# v2_7_Schematic.net
KiCad netlist of a schematic drawn in EAGLE
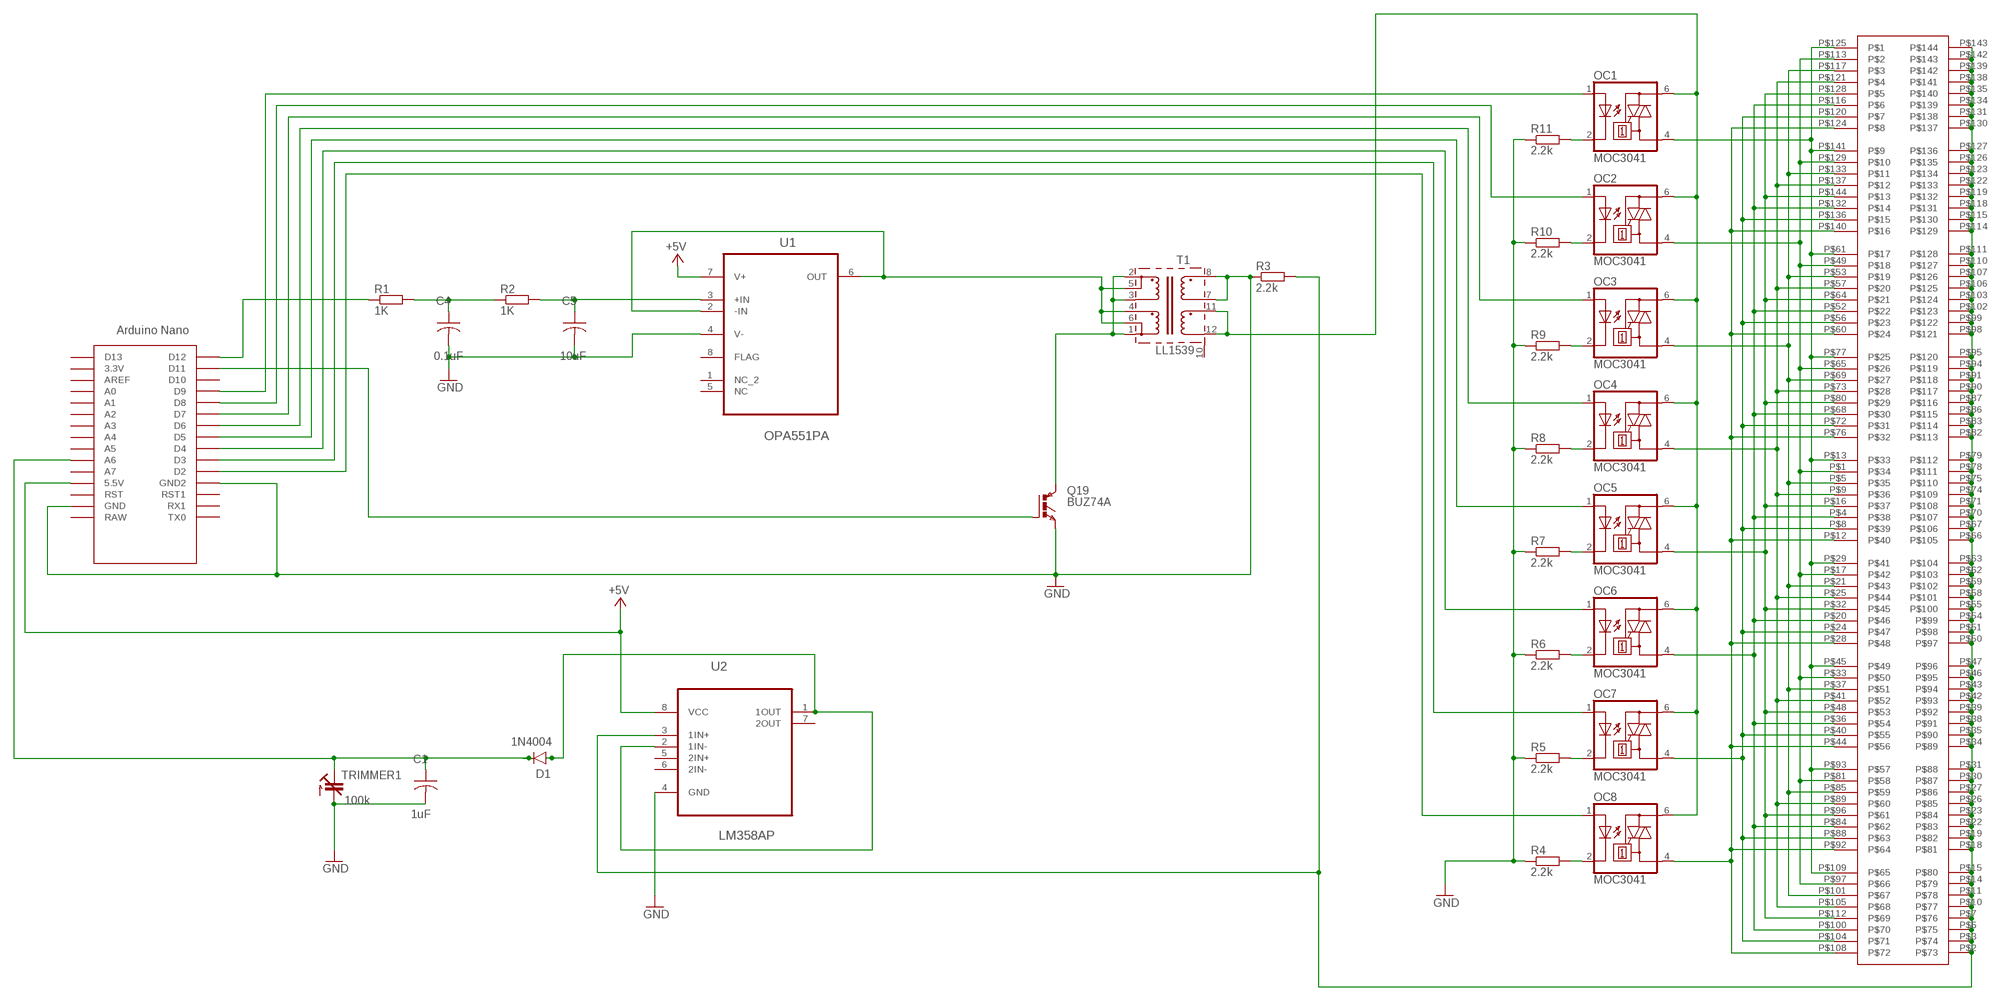
[diagram p0: schematic, sheet 1]

(export (version "E")
  (design (tool "Eeschema 10.0.6"))
  (components
    (comp (ref "C1")
      (value "1uF")
      (footprint "eagle-import:CAP_RADIAL_2MM")
      (fields
        (field (name "DIGIKEY_PART_NUMBER") "P5178-ND")
        (field (name "MANUFACTURER") "Panasonic Electronic Components")
        (field (name "MPN") "ECA-1HM100")
        (field (name "CREATED_BY") "PCBLayout.com")
      )
      (libsource (lib "eagle-import") (part "ECA-1HM100"))
    )
    (comp (ref "C4")
      (value "0.1uF")
      (footprint "eagle-import:CAP_RADIAL_2MM")
      (fields
        (field (name "DIGIKEY_PART_NUMBER") "P5178-ND")
        (field (name "MANUFACTURER") "Panasonic Electronic Components")
        (field (name "MPN") "ECA-1HM100")
        (field (name "CREATED_BY") "PCBLayout.com")
      )
      (libsource (lib "eagle-import") (part "ECA-1HM100"))
    )
    (comp (ref "C5")
      (value "10uF")
      (footprint "eagle-import:CAP_RADIAL_2MM")
      (fields
        (field (name "DIGIKEY_PART_NUMBER") "P5178-ND")
        (field (name "MANUFACTURER") "Panasonic Electronic Components")
        (field (name "MPN") "ECA-1HM100")
        (field (name "CREATED_BY") "PCBLayout.com")
      )
      (libsource (lib "eagle-import") (part "ECA-1HM100"))
    )
    (comp (ref "D1")
      (value "1N4004")
      (footprint "eagle-import:DO-41")
      (fields
        (field (name "DIGIKEY_PART_NUMBER") "1N4004MSCT-ND")
        (field (name "MANUFACTURER") "Micro Commercial Co")
        (field (name "CREATED_BY") "PCBLayout.com")
      )
      (libsource (lib "eagle-import") (part "1N4004"))
    )
    (comp (ref "OC1")
      (value "MOC3041")
      (footprint "eagle-import:DIL06")
      (libsource (lib "eagle-import") (part "MOC3041"))
    )
    (comp (ref "OC2")
      (value "MOC3041")
      (footprint "eagle-import:DIL06")
      (libsource (lib "eagle-import") (part "MOC3041"))
    )
    (comp (ref "OC3")
      (value "MOC3041")
      (footprint "eagle-import:DIL06")
      (libsource (lib "eagle-import") (part "MOC3041"))
    )
    (comp (ref "OC4")
      (value "MOC3041")
      (footprint "eagle-import:DIL06")
      (libsource (lib "eagle-import") (part "MOC3041"))
    )
    (comp (ref "OC5")
      (value "MOC3041")
      (footprint "eagle-import:DIL06")
      (libsource (lib "eagle-import") (part "MOC3041"))
    )
    (comp (ref "OC6")
      (value "MOC3041")
      (footprint "eagle-import:DIL06")
      (libsource (lib "eagle-import") (part "MOC3041"))
    )
    (comp (ref "OC7")
      (value "MOC3041")
      (footprint "eagle-import:DIL06")
      (libsource (lib "eagle-import") (part "MOC3041"))
    )
    (comp (ref "OC8")
      (value "MOC3041")
      (footprint "eagle-import:DIL06")
      (libsource (lib "eagle-import") (part "MOC3041"))
    )
    (comp (ref "Q19")
      (value "BUZ74A")
      (footprint "eagle-import:TO220AV")
      (libsource (lib "eagle-import") (part "IGBTTO220AV"))
    )
    (comp (ref "R1")
      (value "1K")
      (footprint "eagle-import:0204V")
      (libsource (lib "eagle-import") (part "R-EU_0204/2V"))
    )
    (comp (ref "R2")
      (value "1K")
      (footprint "eagle-import:0204V")
      (libsource (lib "eagle-import") (part "R-EU_0204/2V"))
    )
    (comp (ref "R3")
      (value "2.2k")
      (footprint "eagle-import:0204V")
      (libsource (lib "eagle-import") (part "R-EU_0204/2V"))
    )
    (comp (ref "R4")
      (value "2.2k")
      (footprint "eagle-import:0204V")
      (libsource (lib "eagle-import") (part "R-EU_0204/2V"))
    )
    (comp (ref "R5")
      (value "2.2k")
      (footprint "eagle-import:0204V")
      (libsource (lib "eagle-import") (part "R-EU_0204/2V"))
    )
    (comp (ref "R6")
      (value "2.2k")
      (footprint "eagle-import:0204V")
      (libsource (lib "eagle-import") (part "R-EU_0204/2V"))
    )
    (comp (ref "R7")
      (value "2.2k")
      (footprint "eagle-import:0204V")
      (libsource (lib "eagle-import") (part "R-EU_0204/2V"))
    )
    (comp (ref "R8")
      (value "2.2k")
      (footprint "eagle-import:0204V")
      (libsource (lib "eagle-import") (part "R-EU_0204/2V"))
    )
    (comp (ref "R9")
      (value "2.2k")
      (footprint "eagle-import:0204V")
      (libsource (lib "eagle-import") (part "R-EU_0204/2V"))
    )
    (comp (ref "R10")
      (value "2.2k")
      (footprint "eagle-import:0204V")
      (libsource (lib "eagle-import") (part "R-EU_0204/2V"))
    )
    (comp (ref "R11")
      (value "2.2k")
      (footprint "eagle-import:0204V")
      (libsource (lib "eagle-import") (part "R-EU_0204/2V"))
    )
    (comp (ref "T1")
      (value "LL1539")
      (footprint "eagle-import:LL1539")
      (libsource (lib "eagle-import") (part "LL1539"))
    )
    (comp (ref "TRIMMER1")
      (value "100k")
      (footprint "eagle-import:CTRIM3040.452")
      (libsource (lib "eagle-import") (part "C-TRIMM3040.452"))
    )
    (comp (ref "U$1")
      (value "NANO")
      (footprint "eagle-import:NANO")
      (libsource (lib "eagle-import") (part "NANO"))
    )
    (comp (ref "U$2")
      (value "DOTS_V2")
      (footprint "eagle-import:DOTS_V2")
      (libsource (lib "eagle-import") (part "DOTS_V2"))
    )
    (comp (ref "U1")
      (value "OPA551PA")
      (footprint "eagle-import:DIP254P762X508-8")
      (libsource (lib "eagle-import") (part "OPA551PA"))
    )
    (comp (ref "U2")
      (value "LM358AP")
      (footprint "eagle-import:DIP254P762X508-8")
      (libsource (lib "eagle-import") (part "LM358AP"))
    )
  )
  (nets
    (net (code "1") (name "+5V") (class "Default")
      (node (ref "U$1") (pin "5V") (pinfunction "5.5V_5V") (pintype "bidirectional"))
      (node (ref "U1") (pin "7") (pinfunction "V+_7") (pintype "power_in"))
      (node (ref "U2") (pin "8") (pinfunction "VCC_8") (pintype "power_in"))
    )
    (net (code "2") (name "GND") (class "Default")
      (node (ref "C1") (pin "2") (pinfunction "2_2") (pintype "passive"))
      (node (ref "C4") (pin "2") (pinfunction "2_2") (pintype "passive"))
      (node (ref "C5") (pin "2") (pinfunction "2_2") (pintype "passive"))
      (node (ref "Q19") (pin "E") (pinfunction "E_E") (pintype "passive"))
      (node (ref "R10") (pin "1") (pinfunction "1_1") (pintype "passive"))
      (node (ref "R11") (pin "1") (pinfunction "1_1") (pintype "passive"))
      (node (ref "R3") (pin "1") (pinfunction "1_1") (pintype "passive"))
      (node (ref "R4") (pin "1") (pinfunction "1_1") (pintype "passive"))
      (node (ref "R5") (pin "1") (pinfunction "1_1") (pintype "passive"))
      (node (ref "R6") (pin "1") (pinfunction "1_1") (pintype "passive"))
      (node (ref "R7") (pin "1") (pinfunction "1_1") (pintype "passive"))
      (node (ref "R8") (pin "1") (pinfunction "1_1") (pintype "passive"))
      (node (ref "R9") (pin "1") (pinfunction "1_1") (pintype "passive"))
      (node (ref "T1") (pin "7") (pinfunction "7_7") (pintype "passive"))
      (node (ref "T1") (pin "8") (pinfunction "8_8") (pintype "passive"))
      (node (ref "TRIMMER1") (pin "2") (pinfunction "A_2") (pintype "passive"))
      (node (ref "U$1") (pin "GND") (pinfunction "GND_GND") (pintype "bidirectional"))
      (node (ref "U$1") (pin "GND1") (pinfunction "GND2_GND1") (pintype "bidirectional"))
      (node (ref "U1") (pin "4") (pinfunction "V-_4") (pintype "power_in"))
      (node (ref "U2") (pin "4") (pinfunction "GND_4") (pintype "passive"))
    )
    (net (code "3") (name "Net-(C4-Pad1)") (class "Default")
      (node (ref "C4") (pin "1") (pinfunction "1_1") (pintype "passive"))
      (node (ref "R1") (pin "2") (pinfunction "2_2") (pintype "passive"))
      (node (ref "R2") (pin "1") (pinfunction "1_1") (pintype "passive"))
    )
    (net (code "4") (name "Net-(OC1-A)") (class "Default")
      (node (ref "OC1") (pin "1") (pinfunction "A_1") (pintype "passive"))
      (node (ref "U$1") (pin "D9") (pinfunction "D9_D9") (pintype "bidirectional"))
    )
    (net (code "5") (name "Net-(OC1-A1)") (class "Default")
      (node (ref "OC1") (pin "4") (pinfunction "A1_4") (pintype "passive"))
      (node (ref "U$2") (pin "P$109") (pinfunction "P$65_P$109") (pintype "output"))
      (node (ref "U$2") (pin "P$125") (pinfunction "P$1_P$125") (pintype "output"))
      (node (ref "U$2") (pin "P$13") (pinfunction "P$33_P$13") (pintype "output"))
      (node (ref "U$2") (pin "P$141") (pinfunction "P$9_P$141") (pintype "output"))
      (node (ref "U$2") (pin "P$29") (pinfunction "P$41_P$29") (pintype "output"))
      (node (ref "U$2") (pin "P$45") (pinfunction "P$49_P$45") (pintype "output"))
      (node (ref "U$2") (pin "P$61") (pinfunction "P$17_P$61") (pintype "output"))
      (node (ref "U$2") (pin "P$77") (pinfunction "P$25_P$77") (pintype "output"))
      (node (ref "U$2") (pin "P$93") (pinfunction "P$57_P$93") (pintype "output"))
    )
    (net (code "6") (name "Net-(OC1-A2)") (class "Default")
      (node (ref "OC1") (pin "6") (pinfunction "A2_6") (pintype "passive"))
      (node (ref "OC2") (pin "6") (pinfunction "A2_6") (pintype "passive"))
      (node (ref "OC3") (pin "6") (pinfunction "A2_6") (pintype "passive"))
      (node (ref "OC4") (pin "6") (pinfunction "A2_6") (pintype "passive"))
      (node (ref "OC5") (pin "6") (pinfunction "A2_6") (pintype "passive"))
      (node (ref "OC6") (pin "6") (pinfunction "A2_6") (pintype "passive"))
      (node (ref "OC7") (pin "6") (pinfunction "A2_6") (pintype "passive"))
      (node (ref "OC8") (pin "6") (pinfunction "A2_6") (pintype "passive"))
      (node (ref "T1") (pin "11") (pinfunction "11_11") (pintype "passive"))
      (node (ref "T1") (pin "12") (pinfunction "12_12") (pintype "passive"))
    )
    (net (code "7") (name "Net-(OC1-C)") (class "Default")
      (node (ref "OC1") (pin "2") (pinfunction "C_2") (pintype "passive"))
      (node (ref "R11") (pin "2") (pinfunction "2_2") (pintype "passive"))
    )
    (net (code "8") (name "Net-(OC2-A)") (class "Default")
      (node (ref "OC2") (pin "1") (pinfunction "A_1") (pintype "passive"))
      (node (ref "U$1") (pin "D8") (pinfunction "D8_D8") (pintype "bidirectional"))
    )
    (net (code "9") (name "Net-(OC2-A1)") (class "Default")
      (node (ref "OC2") (pin "4") (pinfunction "A1_4") (pintype "passive"))
      (node (ref "U$2") (pin "P$1") (pinfunction "P$34_P$1") (pintype "output"))
      (node (ref "U$2") (pin "P$113") (pinfunction "P$2_P$113") (pintype "output"))
      (node (ref "U$2") (pin "P$129") (pinfunction "P$10_P$129") (pintype "output"))
      (node (ref "U$2") (pin "P$17") (pinfunction "P$42_P$17") (pintype "output"))
      (node (ref "U$2") (pin "P$33") (pinfunction "P$50_P$33") (pintype "output"))
      (node (ref "U$2") (pin "P$49") (pinfunction "P$18_P$49") (pintype "output"))
      (node (ref "U$2") (pin "P$65") (pinfunction "P$26_P$65") (pintype "output"))
      (node (ref "U$2") (pin "P$81") (pinfunction "P$58_P$81") (pintype "output"))
      (node (ref "U$2") (pin "P$97") (pinfunction "P$66_P$97") (pintype "output"))
    )
    (net (code "10") (name "Net-(OC2-C)") (class "Default")
      (node (ref "OC2") (pin "2") (pinfunction "C_2") (pintype "passive"))
      (node (ref "R10") (pin "2") (pinfunction "2_2") (pintype "passive"))
    )
    (net (code "11") (name "Net-(OC3-A)") (class "Default")
      (node (ref "OC3") (pin "1") (pinfunction "A_1") (pintype "passive"))
      (node (ref "U$1") (pin "D7") (pinfunction "D7_D7") (pintype "bidirectional"))
    )
    (net (code "12") (name "Net-(OC3-A1)") (class "Default")
      (node (ref "OC3") (pin "4") (pinfunction "A1_4") (pintype "passive"))
      (node (ref "U$2") (pin "P$101") (pinfunction "P$67_P$101") (pintype "output"))
      (node (ref "U$2") (pin "P$117") (pinfunction "P$3_P$117") (pintype "output"))
      (node (ref "U$2") (pin "P$133") (pinfunction "P$11_P$133") (pintype "output"))
      (node (ref "U$2") (pin "P$21") (pinfunction "P$43_P$21") (pintype "output"))
      (node (ref "U$2") (pin "P$37") (pinfunction "P$51_P$37") (pintype "output"))
      (node (ref "U$2") (pin "P$5") (pinfunction "P$35_P$5") (pintype "output"))
      (node (ref "U$2") (pin "P$53") (pinfunction "P$19_P$53") (pintype "output"))
      (node (ref "U$2") (pin "P$69") (pinfunction "P$27_P$69") (pintype "output"))
      (node (ref "U$2") (pin "P$85") (pinfunction "P$59_P$85") (pintype "output"))
    )
    (net (code "13") (name "Net-(OC3-C)") (class "Default")
      (node (ref "OC3") (pin "2") (pinfunction "C_2") (pintype "passive"))
      (node (ref "R9") (pin "2") (pinfunction "2_2") (pintype "passive"))
    )
    (net (code "14") (name "Net-(OC4-A)") (class "Default")
      (node (ref "OC4") (pin "1") (pinfunction "A_1") (pintype "passive"))
      (node (ref "U$1") (pin "D6") (pinfunction "D6_D6") (pintype "bidirectional"))
    )
    (net (code "15") (name "Net-(OC4-A1)") (class "Default")
      (node (ref "OC4") (pin "4") (pinfunction "A1_4") (pintype "passive"))
      (node (ref "U$2") (pin "P$105") (pinfunction "P$68_P$105") (pintype "output"))
      (node (ref "U$2") (pin "P$121") (pinfunction "P$4_P$121") (pintype "output"))
      (node (ref "U$2") (pin "P$137") (pinfunction "P$12_P$137") (pintype "output"))
      (node (ref "U$2") (pin "P$25") (pinfunction "P$44_P$25") (pintype "output"))
      (node (ref "U$2") (pin "P$41") (pinfunction "P$52_P$41") (pintype "output"))
      (node (ref "U$2") (pin "P$57") (pinfunction "P$20_P$57") (pintype "output"))
      (node (ref "U$2") (pin "P$73") (pinfunction "P$28_P$73") (pintype "output"))
      (node (ref "U$2") (pin "P$89") (pinfunction "P$60_P$89") (pintype "output"))
      (node (ref "U$2") (pin "P$9") (pinfunction "P$36_P$9") (pintype "output"))
    )
    (net (code "16") (name "Net-(OC4-C)") (class "Default")
      (node (ref "OC4") (pin "2") (pinfunction "C_2") (pintype "passive"))
      (node (ref "R8") (pin "2") (pinfunction "2_2") (pintype "passive"))
    )
    (net (code "17") (name "Net-(OC5-A)") (class "Default")
      (node (ref "OC5") (pin "1") (pinfunction "A_1") (pintype "passive"))
      (node (ref "U$1") (pin "D5") (pinfunction "D5_D5") (pintype "bidirectional"))
    )
    (net (code "18") (name "Net-(OC5-A1)") (class "Default")
      (node (ref "OC5") (pin "4") (pinfunction "A1_4") (pintype "passive"))
      (node (ref "U$2") (pin "P$112") (pinfunction "P$69_P$112") (pintype "output"))
      (node (ref "U$2") (pin "P$128") (pinfunction "P$5_P$128") (pintype "output"))
      (node (ref "U$2") (pin "P$144") (pinfunction "P$13_P$144") (pintype "output"))
      (node (ref "U$2") (pin "P$16") (pinfunction "P$37_P$16") (pintype "output"))
      (node (ref "U$2") (pin "P$32") (pinfunction "P$45_P$32") (pintype "output"))
      (node (ref "U$2") (pin "P$48") (pinfunction "P$53_P$48") (pintype "output"))
      (node (ref "U$2") (pin "P$64") (pinfunction "P$21_P$64") (pintype "output"))
      (node (ref "U$2") (pin "P$80") (pinfunction "P$29_P$80") (pintype "output"))
      (node (ref "U$2") (pin "P$96") (pinfunction "P$61_P$96") (pintype "output"))
    )
    (net (code "19") (name "Net-(OC5-C)") (class "Default")
      (node (ref "OC5") (pin "2") (pinfunction "C_2") (pintype "passive"))
      (node (ref "R7") (pin "2") (pinfunction "2_2") (pintype "passive"))
    )
    (net (code "20") (name "Net-(OC6-A)") (class "Default")
      (node (ref "OC6") (pin "1") (pinfunction "A_1") (pintype "passive"))
      (node (ref "U$1") (pin "D4") (pinfunction "D4_D4") (pintype "bidirectional"))
    )
    (net (code "21") (name "Net-(OC6-A1)") (class "Default")
      (node (ref "OC6") (pin "4") (pinfunction "A1_4") (pintype "passive"))
      (node (ref "U$2") (pin "P$100") (pinfunction "P$70_P$100") (pintype "output"))
      (node (ref "U$2") (pin "P$116") (pinfunction "P$6_P$116") (pintype "output"))
      (node (ref "U$2") (pin "P$132") (pinfunction "P$14_P$132") (pintype "output"))
      (node (ref "U$2") (pin "P$20") (pinfunction "P$46_P$20") (pintype "output"))
      (node (ref "U$2") (pin "P$36") (pinfunction "P$54_P$36") (pintype "output"))
      (node (ref "U$2") (pin "P$4") (pinfunction "P$38_P$4") (pintype "output"))
      (node (ref "U$2") (pin "P$52") (pinfunction "P$22_P$52") (pintype "output"))
      (node (ref "U$2") (pin "P$68") (pinfunction "P$30_P$68") (pintype "output"))
      (node (ref "U$2") (pin "P$84") (pinfunction "P$62_P$84") (pintype "output"))
    )
    (net (code "22") (name "Net-(OC6-C)") (class "Default")
      (node (ref "OC6") (pin "2") (pinfunction "C_2") (pintype "passive"))
      (node (ref "R6") (pin "2") (pinfunction "2_2") (pintype "passive"))
    )
    (net (code "23") (name "Net-(OC7-A)") (class "Default")
      (node (ref "OC7") (pin "1") (pinfunction "A_1") (pintype "passive"))
      (node (ref "U$1") (pin "D3") (pinfunction "D3_D3") (pintype "bidirectional"))
    )
    (net (code "24") (name "Net-(OC7-A1)") (class "Default")
      (node (ref "OC7") (pin "4") (pinfunction "A1_4") (pintype "passive"))
      (node (ref "U$2") (pin "P$104") (pinfunction "P$71_P$104") (pintype "output"))
      (node (ref "U$2") (pin "P$120") (pinfunction "P$7_P$120") (pintype "output"))
      (node (ref "U$2") (pin "P$136") (pinfunction "P$15_P$136") (pintype "output"))
      (node (ref "U$2") (pin "P$24") (pinfunction "P$47_P$24") (pintype "output"))
      (node (ref "U$2") (pin "P$40") (pinfunction "P$55_P$40") (pintype "output"))
      (node (ref "U$2") (pin "P$56") (pinfunction "P$23_P$56") (pintype "output"))
      (node (ref "U$2") (pin "P$72") (pinfunction "P$31_P$72") (pintype "output"))
      (node (ref "U$2") (pin "P$8") (pinfunction "P$39_P$8") (pintype "output"))
      (node (ref "U$2") (pin "P$88") (pinfunction "P$63_P$88") (pintype "output"))
    )
    (net (code "25") (name "Net-(OC7-C)") (class "Default")
      (node (ref "OC7") (pin "2") (pinfunction "C_2") (pintype "passive"))
      (node (ref "R5") (pin "2") (pinfunction "2_2") (pintype "passive"))
    )
    (net (code "26") (name "Net-(OC8-A)") (class "Default")
      (node (ref "OC8") (pin "1") (pinfunction "A_1") (pintype "passive"))
      (node (ref "U$1") (pin "D2") (pinfunction "D2_D2") (pintype "bidirectional"))
    )
    (net (code "27") (name "Net-(OC8-A1)") (class "Default")
      (node (ref "OC8") (pin "4") (pinfunction "A1_4") (pintype "passive"))
      (node (ref "U$2") (pin "P$108") (pinfunction "P$72_P$108") (pintype "output"))
      (node (ref "U$2") (pin "P$12") (pinfunction "P$40_P$12") (pintype "output"))
      (node (ref "U$2") (pin "P$124") (pinfunction "P$8_P$124") (pintype "output"))
      (node (ref "U$2") (pin "P$140") (pinfunction "P$16_P$140") (pintype "output"))
      (node (ref "U$2") (pin "P$28") (pinfunction "P$48_P$28") (pintype "output"))
      (node (ref "U$2") (pin "P$44") (pinfunction "P$56_P$44") (pintype "output"))
      (node (ref "U$2") (pin "P$60") (pinfunction "P$24_P$60") (pintype "output"))
      (node (ref "U$2") (pin "P$76") (pinfunction "P$32_P$76") (pintype "output"))
      (node (ref "U$2") (pin "P$92") (pinfunction "P$64_P$92") (pintype "output"))
    )
    (net (code "28") (name "Net-(OC8-C)") (class "Default")
      (node (ref "OC8") (pin "2") (pinfunction "C_2") (pintype "passive"))
      (node (ref "R4") (pin "2") (pinfunction "2_2") (pintype "passive"))
    )
    (net (code "29") (name "Net-(Q19-PadC)") (class "Default")
      (node (ref "Q19") (pin "C") (pinfunction "C_C") (pintype "passive"))
      (node (ref "T1") (pin "1") (pinfunction "1_1") (pintype "passive"))
      (node (ref "T1") (pin "2") (pinfunction "2_2") (pintype "passive"))
      (node (ref "T1") (pin "3") (pinfunction "3_3") (pintype "passive"))
    )
    (net (code "30") (name "Net-(Q19-PadG)") (class "Default")
      (node (ref "Q19") (pin "G") (pinfunction "G_G") (pintype "passive"))
      (node (ref "U$1") (pin "D11") (pinfunction "D11_D11") (pintype "bidirectional"))
    )
    (net (code "31") (name "Net-(R1-Pad1)") (class "Default")
      (node (ref "R1") (pin "1") (pinfunction "1_1") (pintype "passive"))
      (node (ref "U$1") (pin "D12") (pinfunction "D12_D12") (pintype "bidirectional"))
    )
    (net (code "32") (name "Net-(TRIMMER1-E)") (class "Default")
      (node (ref "C1") (pin "1") (pinfunction "1_1") (pintype "passive"))
      (node (ref "D1") (pin "C") (pinfunction "C_C") (pintype "passive"))
      (node (ref "TRIMMER1") (pin "1A") (pinfunction "E_1A") (pintype "passive"))
      (node (ref "U$1") (pin "A6") (pinfunction "A6_A6") (pintype "bidirectional"))
    )
    (net (code "33") (name "Net-(U$2-P$100)") (class "Default")
      (node (ref "R3") (pin "2") (pinfunction "2_2") (pintype "passive"))
      (node (ref "U$2") (pin "P$10") (pinfunction "P$77_P$10") (pintype "power_in"))
      (node (ref "U$2") (pin "P$102") (pinfunction "P$123_P$102") (pintype "power_in"))
      (node (ref "U$2") (pin "P$103") (pinfunction "P$124_P$103") (pintype "power_in"))
      (node (ref "U$2") (pin "P$106") (pinfunction "P$125_P$106") (pintype "power_in"))
      (node (ref "U$2") (pin "P$107") (pinfunction "P$126_P$107") (pintype "power_in"))
      (node (ref "U$2") (pin "P$11") (pinfunction "P$78_P$11") (pintype "power_in"))
      (node (ref "U$2") (pin "P$110") (pinfunction "P$127_P$110") (pintype "power_in"))
      (node (ref "U$2") (pin "P$111") (pinfunction "P$128_P$111") (pintype "power_in"))
      (node (ref "U$2") (pin "P$114") (pinfunction "P$129_P$114") (pintype "power_in"))
      (node (ref "U$2") (pin "P$115") (pinfunction "P$130_P$115") (pintype "power_in"))
      (node (ref "U$2") (pin "P$118") (pinfunction "P$131_P$118") (pintype "power_in"))
      (node (ref "U$2") (pin "P$119") (pinfunction "P$132_P$119") (pintype "power_in"))
      (node (ref "U$2") (pin "P$122") (pinfunction "P$133_P$122") (pintype "power_in"))
      (node (ref "U$2") (pin "P$123") (pinfunction "P$134_P$123") (pintype "power_in"))
      (node (ref "U$2") (pin "P$126") (pinfunction "P$135_P$126") (pintype "power_in"))
      (node (ref "U$2") (pin "P$127") (pinfunction "P$136_P$127") (pintype "power_in"))
      (node (ref "U$2") (pin "P$130") (pinfunction "P$137_P$130") (pintype "power_in"))
      (node (ref "U$2") (pin "P$131") (pinfunction "P$138_P$131") (pintype "power_in"))
      (node (ref "U$2") (pin "P$134") (pinfunction "P$139_P$134") (pintype "power_in"))
      (node (ref "U$2") (pin "P$135") (pinfunction "P$140_P$135") (pintype "power_in"))
      (node (ref "U$2") (pin "P$138") (pinfunction "P$141_P$138") (pintype "power_in"))
      (node (ref "U$2") (pin "P$139") (pinfunction "P$142_P$139") (pintype "power_in"))
      (node (ref "U$2") (pin "P$14") (pinfunction "P$79_P$14") (pintype "power_in"))
      (node (ref "U$2") (pin "P$142") (pinfunction "P$143_P$142") (pintype "power_in"))
      (node (ref "U$2") (pin "P$143") (pinfunction "P$144_P$143") (pintype "power_in"))
      (node (ref "U$2") (pin "P$15") (pinfunction "P$80_P$15") (pintype "power_in"))
      (node (ref "U$2") (pin "P$18") (pinfunction "P$81_P$18") (pintype "power_in"))
      (node (ref "U$2") (pin "P$19") (pinfunction "P$82_P$19") (pintype "power_in"))
      (node (ref "U$2") (pin "P$2") (pinfunction "P$73_P$2") (pintype "power_in"))
      (node (ref "U$2") (pin "P$22") (pinfunction "P$83_P$22") (pintype "power_in"))
      (node (ref "U$2") (pin "P$23") (pinfunction "P$84_P$23") (pintype "power_in"))
      (node (ref "U$2") (pin "P$26") (pinfunction "P$85_P$26") (pintype "power_in"))
      (node (ref "U$2") (pin "P$27") (pinfunction "P$86_P$27") (pintype "power_in"))
      (node (ref "U$2") (pin "P$3") (pinfunction "P$74_P$3") (pintype "power_in"))
      (node (ref "U$2") (pin "P$30") (pinfunction "P$87_P$30") (pintype "power_in"))
      (node (ref "U$2") (pin "P$31") (pinfunction "P$88_P$31") (pintype "power_in"))
      (node (ref "U$2") (pin "P$34") (pinfunction "P$89_P$34") (pintype "power_in"))
      (node (ref "U$2") (pin "P$35") (pinfunction "P$90_P$35") (pintype "power_in"))
      (node (ref "U$2") (pin "P$38") (pinfunction "P$91_P$38") (pintype "power_in"))
      (node (ref "U$2") (pin "P$39") (pinfunction "P$92_P$39") (pintype "power_in"))
      (node (ref "U$2") (pin "P$42") (pinfunction "P$93_P$42") (pintype "power_in"))
      (node (ref "U$2") (pin "P$43") (pinfunction "P$94_P$43") (pintype "power_in"))
      (node (ref "U$2") (pin "P$46") (pinfunction "P$95_P$46") (pintype "power_in"))
      (node (ref "U$2") (pin "P$47") (pinfunction "P$96_P$47") (pintype "power_in"))
      (node (ref "U$2") (pin "P$50") (pinfunction "P$97_P$50") (pintype "power_in"))
      (node (ref "U$2") (pin "P$51") (pinfunction "P$98_P$51") (pintype "power_in"))
      (node (ref "U$2") (pin "P$54") (pinfunction "P$99_P$54") (pintype "power_in"))
      (node (ref "U$2") (pin "P$55") (pinfunction "P$100_P$55") (pintype "power_in"))
      (node (ref "U$2") (pin "P$58") (pinfunction "P$101_P$58") (pintype "power_in"))
      (node (ref "U$2") (pin "P$59") (pinfunction "P$102_P$59") (pintype "power_in"))
      (node (ref "U$2") (pin "P$6") (pinfunction "P$75_P$6") (pintype "power_in"))
      (node (ref "U$2") (pin "P$62") (pinfunction "P$103_P$62") (pintype "power_in"))
      (node (ref "U$2") (pin "P$63") (pinfunction "P$104_P$63") (pintype "power_in"))
      (node (ref "U$2") (pin "P$66") (pinfunction "P$105_P$66") (pintype "power_in"))
      (node (ref "U$2") (pin "P$67") (pinfunction "P$106_P$67") (pintype "power_in"))
      (node (ref "U$2") (pin "P$7") (pinfunction "P$76_P$7") (pintype "power_in"))
      (node (ref "U$2") (pin "P$70") (pinfunction "P$107_P$70") (pintype "power_in"))
      (node (ref "U$2") (pin "P$71") (pinfunction "P$108_P$71") (pintype "power_in"))
      (node (ref "U$2") (pin "P$74") (pinfunction "P$109_P$74") (pintype "power_in"))
      (node (ref "U$2") (pin "P$75") (pinfunction "P$110_P$75") (pintype "power_in"))
      (node (ref "U$2") (pin "P$78") (pinfunction "P$111_P$78") (pintype "power_in"))
      (node (ref "U$2") (pin "P$79") (pinfunction "P$112_P$79") (pintype "power_in"))
      (node (ref "U$2") (pin "P$82") (pinfunction "P$113_P$82") (pintype "power_in"))
      (node (ref "U$2") (pin "P$83") (pinfunction "P$114_P$83") (pintype "power_in"))
      (node (ref "U$2") (pin "P$86") (pinfunction "P$115_P$86") (pintype "power_in"))
      (node (ref "U$2") (pin "P$87") (pinfunction "P$116_P$87") (pintype "power_in"))
      (node (ref "U$2") (pin "P$90") (pinfunction "P$117_P$90") (pintype "power_in"))
      (node (ref "U$2") (pin "P$91") (pinfunction "P$118_P$91") (pintype "power_in"))
      (node (ref "U$2") (pin "P$94") (pinfunction "P$119_P$94") (pintype "power_in"))
      (node (ref "U$2") (pin "P$95") (pinfunction "P$120_P$95") (pintype "power_in"))
      (node (ref "U$2") (pin "P$98") (pinfunction "P$121_P$98") (pintype "power_in"))
      (node (ref "U$2") (pin "P$99") (pinfunction "P$122_P$99") (pintype "power_in"))
      (node (ref "U2") (pin "3") (pinfunction "1IN+_3") (pintype "input"))
    )
    (net (code "34") (name "Net-(U1-+IN)") (class "Default")
      (node (ref "C5") (pin "1") (pinfunction "1_1") (pintype "passive"))
      (node (ref "R2") (pin "2") (pinfunction "2_2") (pintype "passive"))
      (node (ref "U1") (pin "3") (pinfunction "+IN_3") (pintype "input"))
    )
    (net (code "35") (name "Net-(U1--IN)") (class "Default")
      (node (ref "T1") (pin "4") (pinfunction "4_4") (pintype "passive"))
      (node (ref "T1") (pin "5") (pinfunction "5_5") (pintype "passive"))
      (node (ref "T1") (pin "6") (pinfunction "6_6") (pintype "passive"))
      (node (ref "U1") (pin "2") (pinfunction "-IN_2") (pintype "input"))
      (node (ref "U1") (pin "6") (pinfunction "OUT_6") (pintype "output"))
    )
    (net (code "36") (name "Net-(U2-1IN-)") (class "Default")
      (node (ref "D1") (pin "A") (pinfunction "A_A") (pintype "passive"))
      (node (ref "U2") (pin "1") (pinfunction "1OUT_1") (pintype "output"))
      (node (ref "U2") (pin "2") (pinfunction "1IN-_2") (pintype "input"))
    )
    (net (code "37") (name "unconnected-(T1-Pad10)") (class "Default")
      (node (ref "T1") (pin "10") (pinfunction "10_10") (pintype "passive"))
    )
    (net (code "38") (name "unconnected-(U$1-Pad3.3V)") (class "Default")
      (node (ref "U$1") (pin "3.3V") (pinfunction "3.3V_3.3V") (pintype "bidirectional"))
    )
    (net (code "39") (name "unconnected-(U$1-PadA0)") (class "Default")
      (node (ref "U$1") (pin "A0") (pinfunction "A0_A0") (pintype "bidirectional"))
    )
    (net (code "40") (name "unconnected-(U$1-PadA1)") (class "Default")
      (node (ref "U$1") (pin "A1") (pinfunction "A1_A1") (pintype "bidirectional"))
    )
    (net (code "41") (name "unconnected-(U$1-PadA2)") (class "Default")
      (node (ref "U$1") (pin "A2") (pinfunction "A2_A2") (pintype "bidirectional"))
    )
    (net (code "42") (name "unconnected-(U$1-PadA3)") (class "Default")
      (node (ref "U$1") (pin "A3") (pinfunction "A3_A3") (pintype "bidirectional"))
    )
    (net (code "43") (name "unconnected-(U$1-PadA4)") (class "Default")
      (node (ref "U$1") (pin "A4") (pinfunction "A4_A4") (pintype "bidirectional"))
    )
    (net (code "44") (name "unconnected-(U$1-PadA5)") (class "Default")
      (node (ref "U$1") (pin "A5") (pinfunction "A5_A5") (pintype "bidirectional"))
    )
    (net (code "45") (name "unconnected-(U$1-PadA7)") (class "Default")
      (node (ref "U$1") (pin "A7") (pinfunction "A7_A7") (pintype "bidirectional"))
    )
    (net (code "46") (name "unconnected-(U$1-PadAREF)") (class "Default")
      (node (ref "U$1") (pin "AREF") (pinfunction "AREF_AREF") (pintype "bidirectional"))
    )
    (net (code "47") (name "unconnected-(U$1-PadD10)") (class "Default")
      (node (ref "U$1") (pin "D10") (pinfunction "D10_D10") (pintype "bidirectional"))
    )
    (net (code "48") (name "unconnected-(U$1-PadD13)") (class "Default")
      (node (ref "U$1") (pin "D13") (pinfunction "D13_D13") (pintype "bidirectional"))
    )
    (net (code "49") (name "unconnected-(U$1-PadRAW)") (class "Default")
      (node (ref "U$1") (pin "RAW") (pinfunction "RAW_RAW") (pintype "bidirectional"))
    )
    (net (code "50") (name "unconnected-(U$1-PadRST)") (class "Default")
      (node (ref "U$1") (pin "RST") (pinfunction "RST_RST") (pintype "bidirectional"))
    )
    (net (code "51") (name "unconnected-(U$1-PadRST1)") (class "Default")
      (node (ref "U$1") (pin "RST1") (pinfunction "RST1_RST1") (pintype "bidirectional"))
    )
    (net (code "52") (name "unconnected-(U$1-PadRX1)") (class "Default")
      (node (ref "U$1") (pin "RX1") (pinfunction "RX1_RX1") (pintype "bidirectional"))
    )
    (net (code "53") (name "unconnected-(U$1-PadTX0)") (class "Default")
      (node (ref "U$1") (pin "TX0") (pinfunction "TX0_TX0") (pintype "bidirectional"))
    )
    (net (code "54") (name "unconnected-(U1-FLAG-Pad8)") (class "Default")
      (node (ref "U1") (pin "8") (pinfunction "FLAG_8") (pintype "passive"))
    )
    (net (code "55") (name "unconnected-(U1-NC-Pad5)") (class "Default")
      (node (ref "U1") (pin "5") (pinfunction "NC_5") (pintype "no_connect"))
    )
    (net (code "56") (name "unconnected-(U1-NC_2-Pad1)") (class "Default")
      (node (ref "U1") (pin "1") (pinfunction "NC_2_1") (pintype "no_connect"))
    )
    (net (code "57") (name "unconnected-(U2-2IN+-Pad5)") (class "Default")
      (node (ref "U2") (pin "5") (pinfunction "2IN+_5") (pintype "input"))
    )
    (net (code "58") (name "unconnected-(U2-2IN--Pad6)") (class "Default")
      (node (ref "U2") (pin "6") (pinfunction "2IN-_6") (pintype "input"))
    )
    (net (code "59") (name "unconnected-(U2-2OUT-Pad7)") (class "Default")
      (node (ref "U2") (pin "7") (pinfunction "2OUT_7") (pintype "output"))
    )
  )
)
